# untitled.net
KiCad netlist of a schematic drawn in EAGLE
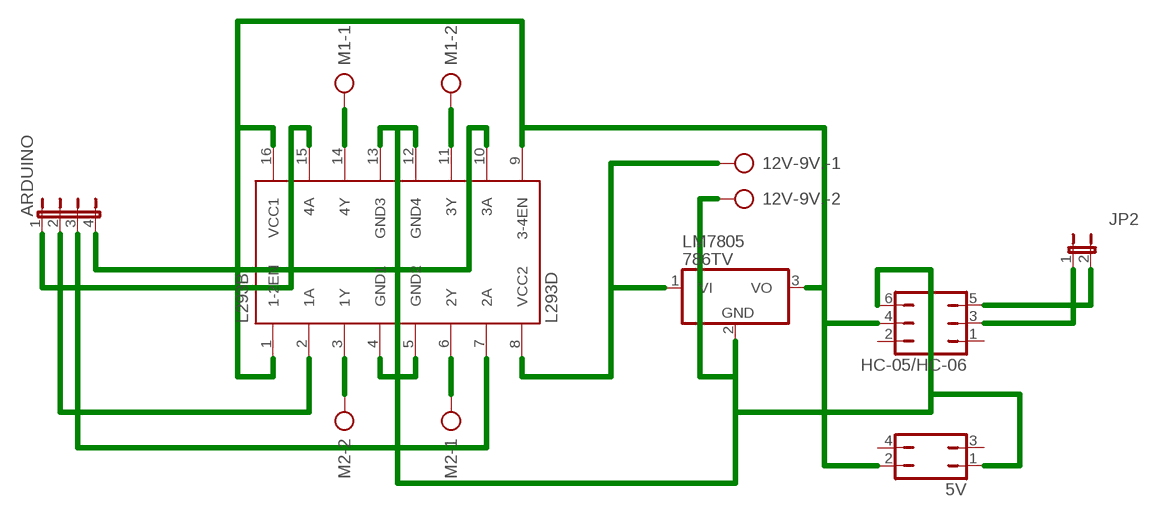
[diagram p0: schematic, sheet 1]

(export (version "E")
  (design (tool "Eeschema 10.0.6"))
  (components
    (comp (ref "5V")
      (value "JP2Q")
      (footprint "eagle-import:5V-ARDUINO-OKIOKIS")
      (libsource (lib "eagle-import") (part "JP2Q"))
    )
    (comp (ref "12V-9V.")
      (value "AK300/2-OKIS")
      (footprint "eagle-import:AK300_2-OKIS")
      (libsource (lib "eagle-import") (part "AK300/2-OKIS"))
    )
    (comp (ref "ARDUINO")
      (value "JP4E")
      (footprint "eagle-import:ARDUINO-2021-0KIS-SI-O-SI")
      (libsource (lib "eagle-import") (part "JP4E"))
    )
    (comp (ref "HC-05/HC-06")
      (value "JP3Q")
      (footprint "eagle-import:HC-05-HC-06-OKISOKISS")
      (libsource (lib "eagle-import") (part "JP3Q"))
    )
    (comp (ref "JP2")
      (value "JP1E")
      (footprint "eagle-import:2-PINES-OK-2021-TX-RX")
      (libsource (lib "eagle-import") (part "JP1E"))
    )
    (comp (ref "L293B")
      (value "L293D")
      (footprint "eagle-import:DIL16")
      (libsource (lib "eagle-import") (part "L293D"))
    )
    (comp (ref "LM7805")
      (value "786TV")
      (footprint "eagle-import:LM7812_OK")
      (libsource (lib "eagle-import") (part "78TV6"))
    )
    (comp (ref "M1")
      (value "AK300/2-OKIS")
      (footprint "eagle-import:AK300_2-OKIS")
      (libsource (lib "eagle-import") (part "AK300/2-OKIS"))
    )
    (comp (ref "M2")
      (value "AK300/2-OKIS")
      (footprint "eagle-import:AK300_2-OKIS")
      (libsource (lib "eagle-import") (part "AK300/2-OKIS"))
    )
  )
  (nets
    (net (code "1") (name "Net-(12V-9V.A-KL)") (class "Default")
      (node (ref "12V-9V.") (pin "1") (pinfunction "KL_1") (pintype "passive"))
      (node (ref "L293B") (pin "8") (pinfunction "VCC2_8") (pintype "power_in"))
      (node (ref "LM7805") (pin "1") (pinfunction "VI_1") (pintype "input"))
    )
    (net (code "2") (name "Net-(12V-9V.B-KL)") (class "Default")
      (node (ref "12V-9V.") (pin "2") (pinfunction "KL_2") (pintype "passive"))
      (node (ref "5V") (pin "1") (pinfunction "1_1") (pintype "passive"))
      (node (ref "HC-05/HC-06") (pin "6") (pinfunction "6_6") (pintype "passive"))
      (node (ref "L293B") (pin "12") (pinfunction "GND4_12") (pintype "power_in"))
      (node (ref "L293B") (pin "13") (pinfunction "GND3_13") (pintype "power_in"))
      (node (ref "L293B") (pin "4") (pinfunction "GND1_4") (pintype "power_in"))
      (node (ref "L293B") (pin "5") (pinfunction "GND2_5") (pintype "power_in"))
      (node (ref "LM7805") (pin "2") (pinfunction "GND_2") (pintype "passive"))
    )
    (net (code "3") (name "Net-(HC-05/HC-06-Pad3)") (class "Default")
      (node (ref "HC-05/HC-06") (pin "3") (pinfunction "3_3") (pintype "passive"))
      (node (ref "JP2") (pin "1") (pinfunction "1_1") (pintype "passive"))
    )
    (net (code "4") (name "Net-(HC-05/HC-06-Pad5)") (class "Default")
      (node (ref "HC-05/HC-06") (pin "5") (pinfunction "5_5") (pintype "passive"))
      (node (ref "JP2") (pin "2") (pinfunction "2_2") (pintype "passive"))
    )
    (net (code "5") (name "Net-(L293B-1-2EN)") (class "Default")
      (node (ref "5V") (pin "2") (pinfunction "2_2") (pintype "passive"))
      (node (ref "HC-05/HC-06") (pin "4") (pinfunction "4_4") (pintype "passive"))
      (node (ref "L293B") (pin "1") (pinfunction "1-2EN_1") (pintype "input"))
      (node (ref "L293B") (pin "16") (pinfunction "VCC1_16") (pintype "power_in"))
      (node (ref "L293B") (pin "9") (pinfunction "3-4EN_9") (pintype "input"))
      (node (ref "LM7805") (pin "3") (pinfunction "VO_3") (pintype "passive"))
    )
    (net (code "6") (name "Net-(L293B-1A)") (class "Default")
      (node (ref "ARDUINO") (pin "2") (pinfunction "2_2") (pintype "passive"))
      (node (ref "L293B") (pin "2") (pinfunction "1A_2") (pintype "input"))
    )
    (net (code "7") (name "Net-(L293B-1Y)") (class "Default")
      (node (ref "L293B") (pin "3") (pinfunction "1Y_3") (pintype "output"))
      (node (ref "M2") (pin "2") (pinfunction "KL_2") (pintype "passive"))
    )
    (net (code "8") (name "Net-(L293B-2A)") (class "Default")
      (node (ref "ARDUINO") (pin "3") (pinfunction "3_3") (pintype "passive"))
      (node (ref "L293B") (pin "7") (pinfunction "2A_7") (pintype "input"))
    )
    (net (code "9") (name "Net-(L293B-2Y)") (class "Default")
      (node (ref "L293B") (pin "6") (pinfunction "2Y_6") (pintype "output"))
      (node (ref "M2") (pin "1") (pinfunction "KL_1") (pintype "passive"))
    )
    (net (code "10") (name "Net-(L293B-3A)") (class "Default")
      (node (ref "ARDUINO") (pin "4") (pinfunction "4_4") (pintype "passive"))
      (node (ref "L293B") (pin "10") (pinfunction "3A_10") (pintype "input"))
    )
    (net (code "11") (name "Net-(L293B-3Y)") (class "Default")
      (node (ref "L293B") (pin "11") (pinfunction "3Y_11") (pintype "output"))
      (node (ref "M1") (pin "2") (pinfunction "KL_2") (pintype "passive"))
    )
    (net (code "12") (name "Net-(L293B-4A)") (class "Default")
      (node (ref "ARDUINO") (pin "1") (pinfunction "1_1") (pintype "passive"))
      (node (ref "L293B") (pin "15") (pinfunction "4A_15") (pintype "input"))
    )
    (net (code "13") (name "Net-(L293B-4Y)") (class "Default")
      (node (ref "L293B") (pin "14") (pinfunction "4Y_14") (pintype "output"))
      (node (ref "M1") (pin "1") (pinfunction "KL_1") (pintype "passive"))
    )
    (net (code "14") (name "unconnected-(5V-Pad3)") (class "Default")
      (node (ref "5V") (pin "3") (pinfunction "3_3") (pintype "passive"))
    )
    (net (code "15") (name "unconnected-(5V-Pad4)") (class "Default")
      (node (ref "5V") (pin "4") (pinfunction "4_4") (pintype "passive"))
    )
    (net (code "16") (name "unconnected-(HC-05/HC-06-Pad1)") (class "Default")
      (node (ref "HC-05/HC-06") (pin "1") (pinfunction "1_1") (pintype "passive"))
    )
    (net (code "17") (name "unconnected-(HC-05/HC-06-Pad2)") (class "Default")
      (node (ref "HC-05/HC-06") (pin "2") (pinfunction "2_2") (pintype "passive"))
    )
  )
)
